# V2.net
KiCad netlist of a schematic drawn in EAGLE
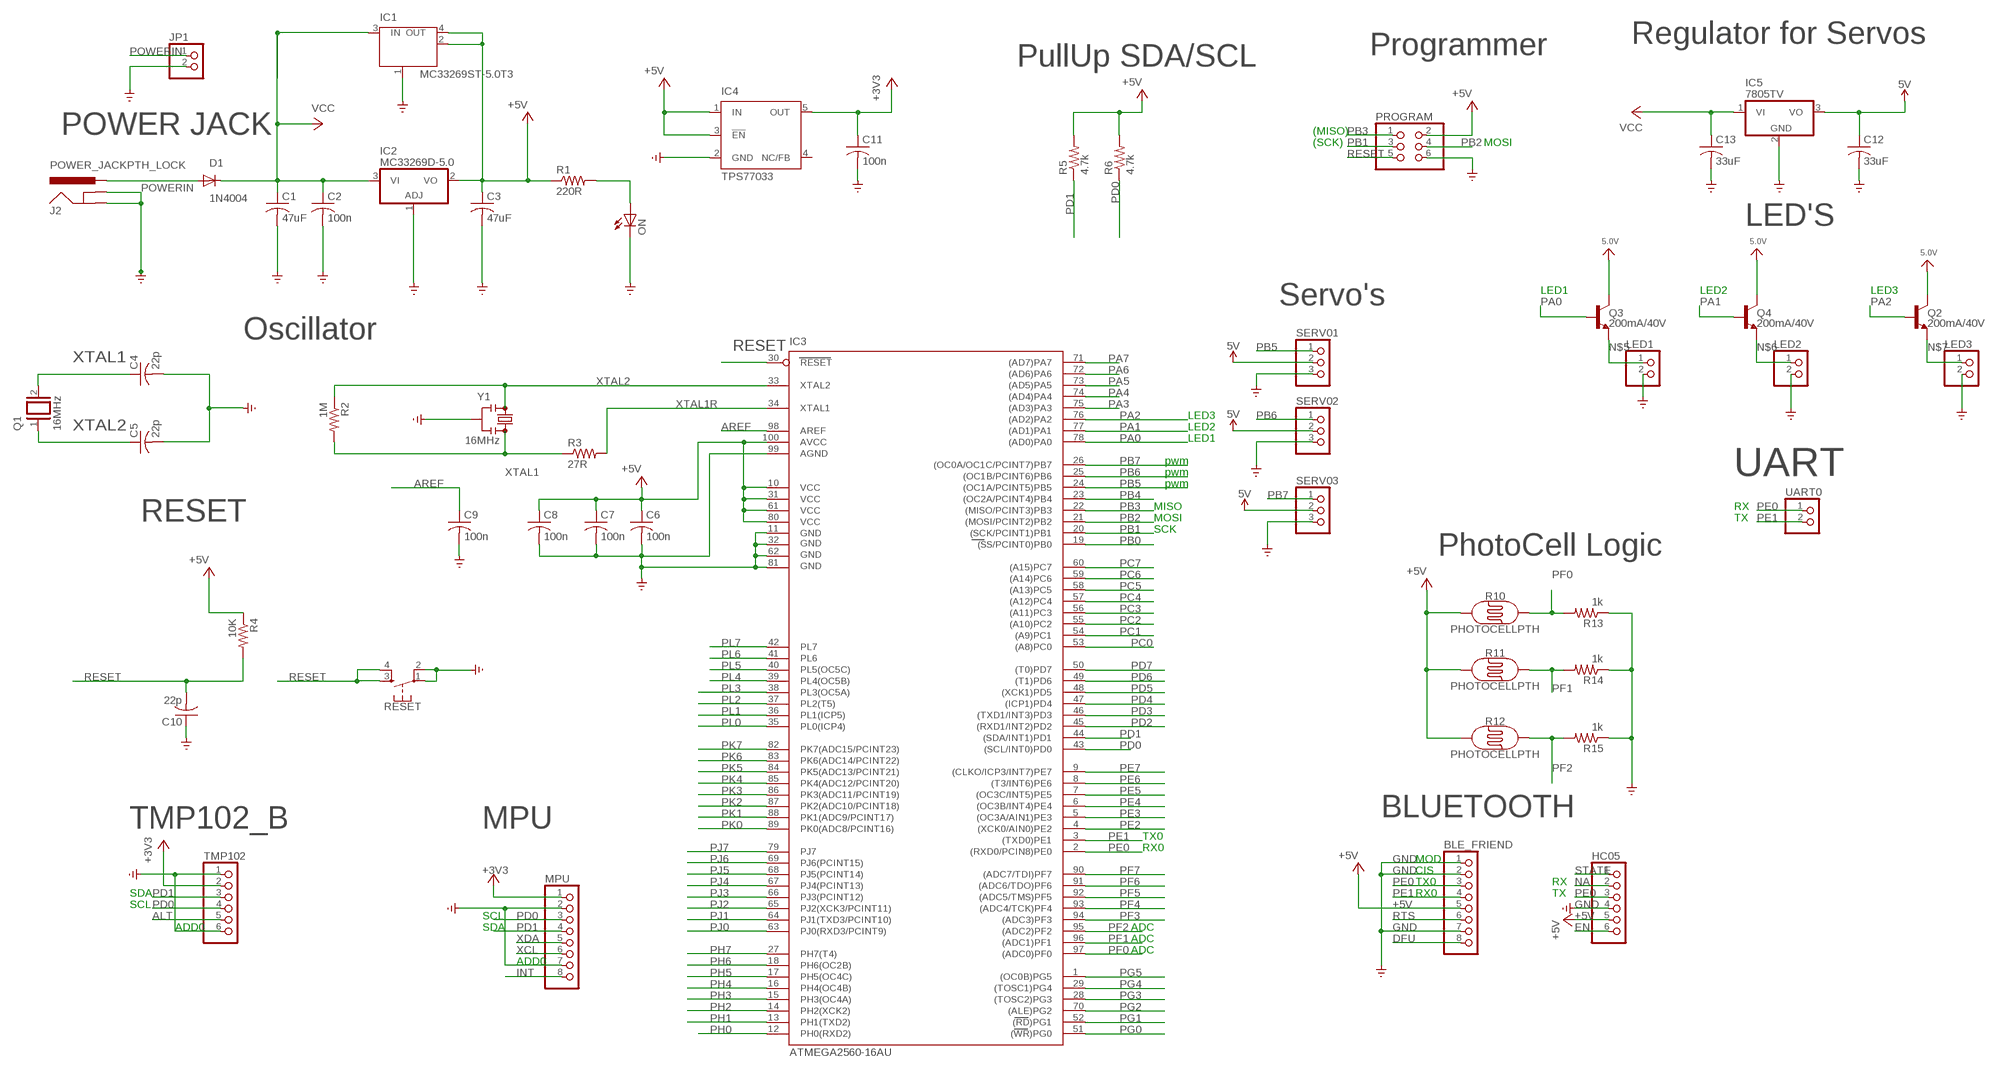
[diagram p0: schematic, sheet 1, part 1 of 2]
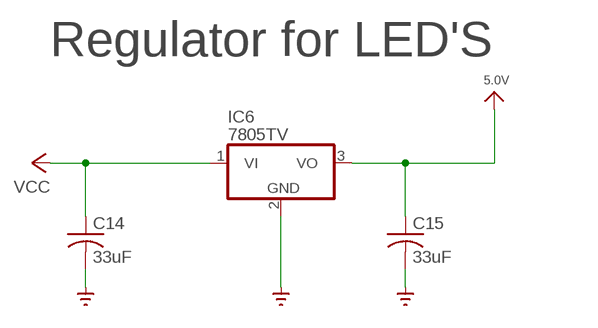
[diagram p1: schematic, sheet 1, part 2 of 2]

(export (version "E")
  (design (tool "Eeschema 10.0.6"))
  (components
    (comp (ref "BLE_FRIEND")
      (value "PINHD-1X8")
      (footprint "eagle-import:1X08")
      (libsource (lib "eagle-import") (part "PINHD-1X8"))
    )
    (comp (ref "C1")
      (value "47uF")
      (footprint "eagle-import:C025-024X044")
      (libsource (lib "eagle-import") (part "C-US025-024X044"))
    )
    (comp (ref "C2")
      (value "100n")
      (footprint "eagle-import:C025-024X044")
      (libsource (lib "eagle-import") (part "C-US025-024X044"))
    )
    (comp (ref "C3")
      (value "47uF")
      (footprint "eagle-import:C025-024X044")
      (libsource (lib "eagle-import") (part "C-US025-024X044"))
    )
    (comp (ref "C4")
      (value "22p")
      (footprint "eagle-import:C025-024X044")
      (libsource (lib "eagle-import") (part "C-US025-024X044"))
    )
    (comp (ref "C5")
      (value "22p")
      (footprint "eagle-import:C025-024X044")
      (libsource (lib "eagle-import") (part "C-US025-024X044"))
    )
    (comp (ref "C6")
      (value "100n")
      (footprint "eagle-import:C025-024X044")
      (libsource (lib "eagle-import") (part "C-US025-024X044"))
    )
    (comp (ref "C7")
      (value "100n")
      (footprint "eagle-import:C025-024X044")
      (libsource (lib "eagle-import") (part "C-US025-024X044"))
    )
    (comp (ref "C8")
      (value "100n")
      (footprint "eagle-import:C025-024X044")
      (libsource (lib "eagle-import") (part "C-US025-024X044"))
    )
    (comp (ref "C9")
      (value "100n")
      (footprint "eagle-import:C025-024X044")
      (libsource (lib "eagle-import") (part "C-US025-024X044"))
    )
    (comp (ref "C10")
      (value "22p")
      (footprint "eagle-import:C025-024X044")
      (libsource (lib "eagle-import") (part "C-US025-024X044"))
    )
    (comp (ref "C11")
      (value "100n")
      (footprint "eagle-import:C025-024X044")
      (libsource (lib "eagle-import") (part "C-US025-024X044"))
    )
    (comp (ref "C12")
      (value "33uF")
      (footprint "eagle-import:C025-024X044")
      (libsource (lib "eagle-import") (part "C-US025-024X044"))
    )
    (comp (ref "C13")
      (value "33uF")
      (footprint "eagle-import:C025-024X044")
      (libsource (lib "eagle-import") (part "C-US025-024X044"))
    )
    (comp (ref "C14")
      (value "33uF")
      (footprint "eagle-import:C025-024X044")
      (libsource (lib "eagle-import") (part "C-US025-024X044"))
    )
    (comp (ref "C15")
      (value "33uF")
      (footprint "eagle-import:C025-024X044")
      (libsource (lib "eagle-import") (part "C-US025-024X044"))
    )
    (comp (ref "D1")
      (value "1N4004")
      (footprint "eagle-import:DO41-10")
      (libsource (lib "eagle-import") (part "1N4004"))
    )
    (comp (ref "HC05")
      (value "PINHD-1X6")
      (footprint "eagle-import:1X06")
      (libsource (lib "eagle-import") (part "pinhead_325_PINHD-1X6"))
    )
    (comp (ref "IC1")
      (value "MC33269ST-5.0T3")
      (footprint "eagle-import:SOT223")
      (libsource (lib "eagle-import") (part "MC33269ST-3.3T3"))
    )
    (comp (ref "IC2")
      (value "MC33269D-5.0")
      (footprint "eagle-import:DPACK")
      (libsource (lib "eagle-import") (part "MC33269?D-5.0"))
    )
    (comp (ref "IC3")
      (value "ATMEGA2560-16AU")
      (footprint "eagle-import:TQFP100")
      (libsource (lib "eagle-import") (part "ATMEGAAU2560-16"))
    )
    (comp (ref "IC4")
      (value "TPS77033")
      (footprint "eagle-import:SOT23-DBV")
      (fields (field (name "MF") "TEXAS INSTRUMENTS") (field (name "MPN") "TPS77033DBVT"))
      (libsource (lib "eagle-import") (part "TPS77033"))
    )
    (comp (ref "IC5")
      (value "7805TV")
      (footprint "eagle-import:TO220V")
      (libsource (lib "eagle-import") (part "78TV05"))
    )
    (comp (ref "IC6")
      (value "7805TV")
      (footprint "eagle-import:TO220V")
      (libsource (lib "eagle-import") (part "78TV05"))
    )
    (comp (ref "J2")
      (value "POWER_JACKPTH_LOCK")
      (footprint "eagle-import:POWER_JACK_PTH_LOCK")
      (libsource (lib "eagle-import") (part "POWER_JACKPTH_LOCK"))
    )
    (comp (ref "JP1")
      (value "PINHD-1X2")
      (footprint "eagle-import:1X02")
      (libsource (lib "eagle-import") (part "pinhead_325_PINHD-1X2"))
    )
    (comp (ref "LED1")
      (value "PINHD-1X2")
      (footprint "eagle-import:1X02")
      (libsource (lib "eagle-import") (part "PINHD-1X2"))
    )
    (comp (ref "LED2")
      (value "PINHD-1X2")
      (footprint "eagle-import:1X02")
      (libsource (lib "eagle-import") (part "PINHD-1X2"))
    )
    (comp (ref "LED3")
      (value "PINHD-1X2")
      (footprint "eagle-import:1X02")
      (libsource (lib "eagle-import") (part "PINHD-1X2"))
    )
    (comp (ref "MPU")
      (value "PINHD-1X8")
      (footprint "eagle-import:1X08")
      (libsource (lib "eagle-import") (part "PINHD-1X8"))
    )
    (comp (ref "ON")
      (value "LED3MM")
      (footprint "eagle-import:LED3MM")
      (libsource (lib "eagle-import") (part "LED3MM"))
    )
    (comp (ref "PROGRAM")
      (value "PINHD-2X3")
      (footprint "eagle-import:2X03")
      (libsource (lib "eagle-import") (part "PINHD-2X3"))
    )
    (comp (ref "Q1")
      (value "16MHz")
      (footprint "eagle-import:QS")
      (libsource (lib "eagle-import") (part "XTAL/S"))
    )
    (comp (ref "Q2")
      (value "200mA/40V")
      (footprint "eagle-import:TO-92")
      (libsource (lib "eagle-import") (part "TRANS_NPN-2N3904"))
    )
    (comp (ref "Q3")
      (value "200mA/40V")
      (footprint "eagle-import:TO-92")
      (libsource (lib "eagle-import") (part "TRANS_NPN-2N3904"))
    )
    (comp (ref "Q4")
      (value "200mA/40V")
      (footprint "eagle-import:TO-92")
      (libsource (lib "eagle-import") (part "TRANS_NPN-2N3904"))
    )
    (comp (ref "R1")
      (value "220R")
      (footprint "eagle-import:0204V")
      (libsource (lib "eagle-import") (part "R-US_0204/2V"))
    )
    (comp (ref "R2")
      (value "1M")
      (footprint "eagle-import:0204V")
      (libsource (lib "eagle-import") (part "R-US_0204/2V"))
    )
    (comp (ref "R3")
      (value "27R")
      (footprint "eagle-import:0204V")
      (libsource (lib "eagle-import") (part "R-US_0204/2V"))
    )
    (comp (ref "R4")
      (value "10K")
      (footprint "eagle-import:0204V")
      (libsource (lib "eagle-import") (part "R-US_0204/2V"))
    )
    (comp (ref "R5")
      (value "4.7k")
      (footprint "eagle-import:0204V")
      (libsource (lib "eagle-import") (part "R-US_0204/2V"))
    )
    (comp (ref "R6")
      (value "4.7k")
      (footprint "eagle-import:0204V")
      (libsource (lib "eagle-import") (part "R-US_0204/2V"))
    )
    (comp (ref "R10")
      (value "PHOTOCELLPTH")
      (footprint "eagle-import:PHOTOCELL")
      (libsource (lib "eagle-import") (part "PHOTOCELLPTH"))
    )
    (comp (ref "R11")
      (value "PHOTOCELLPTH")
      (footprint "eagle-import:PHOTOCELL")
      (libsource (lib "eagle-import") (part "PHOTOCELLPTH"))
    )
    (comp (ref "R12")
      (value "PHOTOCELLPTH")
      (footprint "eagle-import:PHOTOCELL")
      (libsource (lib "eagle-import") (part "PHOTOCELLPTH"))
    )
    (comp (ref "R13")
      (value "1k")
      (footprint "eagle-import:0204V")
      (libsource (lib "eagle-import") (part "R-US_0204/2V"))
    )
    (comp (ref "R14")
      (value "1k")
      (footprint "eagle-import:0204V")
      (libsource (lib "eagle-import") (part "R-US_0204/2V"))
    )
    (comp (ref "R15")
      (value "1k")
      (footprint "eagle-import:0204V")
      (libsource (lib "eagle-import") (part "R-US_0204/2V"))
    )
    (comp (ref "RESET")
      (value "MOMENTARY-SWITCH-SPST-2-SMD-5.2MM")
      (footprint "eagle-import:TACTILE_SWITCH_SMD_5.2MM")
      (libsource (lib "eagle-import") (part "MOMENTARY-SWITCH-SPST-2-SMD-5.2MM"))
    )
    (comp (ref "SERV01")
      (value "PINHD-1X3")
      (footprint "eagle-import:1X03")
      (libsource (lib "eagle-import") (part "PINHD-1X3"))
    )
    (comp (ref "SERV02")
      (value "PINHD-1X3")
      (footprint "eagle-import:1X03")
      (libsource (lib "eagle-import") (part "PINHD-1X3"))
    )
    (comp (ref "SERV03")
      (value "PINHD-1X3")
      (footprint "eagle-import:1X03")
      (libsource (lib "eagle-import") (part "PINHD-1X3"))
    )
    (comp (ref "TMP102")
      (value "PINHD-1X6")
      (footprint "eagle-import:1X06")
      (libsource (lib "eagle-import") (part "PINHD-1X6"))
    )
    (comp (ref "UART0")
      (value "PINHD-1X2")
      (footprint "eagle-import:1X02")
      (libsource (lib "eagle-import") (part "PINHD-1X2"))
    )
    (comp (ref "Y1")
      (value "16MHz")
      (footprint "eagle-import:RESONATOR-SMD-3.2X1.3")
      (libsource (lib "eagle-import") (part "RESONATORSMD-3.2X1.3"))
    )
  )
  (nets
    (net (code "1") (name "+3V3") (class "Default")
      (node (ref "C11") (pin "1") (pinfunction "1_1") (pintype "passive"))
      (node (ref "IC4") (pin "5") (pinfunction "OUT_5") (pintype "passive"))
      (node (ref "MPU") (pin "1") (pinfunction "1_1") (pintype "passive"))
      (node (ref "TMP102") (pin "2") (pinfunction "2_2") (pintype "passive"))
    )
    (net (code "2") (name "+5V") (class "Default")
      (node (ref "BLE_FRIEND") (pin "5") (pinfunction "5_5") (pintype "passive"))
      (node (ref "C3") (pin "1") (pinfunction "1_1") (pintype "passive"))
      (node (ref "C6") (pin "1") (pinfunction "1_1") (pintype "passive"))
      (node (ref "C7") (pin "1") (pinfunction "1_1") (pintype "passive"))
      (node (ref "C8") (pin "1") (pinfunction "1_1") (pintype "passive"))
      (node (ref "HC05") (pin "5") (pinfunction "5_5") (pintype "passive"))
      (node (ref "IC1") (pin "2") (pinfunction "OUT_2") (pintype "passive"))
      (node (ref "IC1") (pin "4") (pinfunction "OUT_4") (pintype "passive"))
      (node (ref "IC2") (pin "2") (pinfunction "VO_2") (pintype "passive"))
      (node (ref "IC3") (pin "10") (pinfunction "VCC_10") (pintype "power_in"))
      (node (ref "IC3") (pin "100") (pinfunction "AVCC_100") (pintype "power_in"))
      (node (ref "IC3") (pin "31") (pinfunction "VCC1_31") (pintype "power_in"))
      (node (ref "IC3") (pin "61") (pinfunction "VCC2_61") (pintype "power_in"))
      (node (ref "IC3") (pin "80") (pinfunction "VCC3_80") (pintype "power_in"))
      (node (ref "IC4") (pin "1") (pinfunction "IN_1") (pintype "input"))
      (node (ref "IC4") (pin "3") (pinfunction "~{EN}_3") (pintype "input"))
      (node (ref "PROGRAM") (pin "2") (pinfunction "2_2") (pintype "passive"))
      (node (ref "R1") (pin "1") (pinfunction "1_1") (pintype "passive"))
      (node (ref "R10") (pin "1") (pinfunction "P$1_1") (pintype "bidirectional"))
      (node (ref "R11") (pin "1") (pinfunction "P$1_1") (pintype "bidirectional"))
      (node (ref "R12") (pin "1") (pinfunction "P$1_1") (pintype "bidirectional"))
      (node (ref "R4") (pin "1") (pinfunction "1_1") (pintype "passive"))
      (node (ref "R5") (pin "2") (pinfunction "2_2") (pintype "passive"))
      (node (ref "R6") (pin "2") (pinfunction "2_2") (pintype "passive"))
    )
    (net (code "3") (name "/ALT") (class "Default")
      (node (ref "TMP102") (pin "5") (pinfunction "5_5") (pintype "passive"))
    )
    (net (code "4") (name "/AREF") (class "Default")
      (node (ref "C9") (pin "1") (pinfunction "1_1") (pintype "passive"))
      (node (ref "IC3") (pin "98") (pinfunction "AREF_98") (pintype "bidirectional"))
    )
    (net (code "5") (name "/DFU") (class "Default")
      (node (ref "BLE_FRIEND") (pin "8") (pinfunction "8_8") (pintype "passive"))
    )
    (net (code "6") (name "/EN") (class "Default")
      (node (ref "HC05") (pin "6") (pinfunction "6_6") (pintype "passive"))
    )
    (net (code "7") (name "/INT") (class "Default")
      (node (ref "MPU") (pin "8") (pinfunction "8_8") (pintype "passive"))
    )
    (net (code "8") (name "/N$5") (class "Default")
      (node (ref "LED1") (pin "1") (pinfunction "1_1") (pintype "passive"))
      (node (ref "Q3") (pin "1") (pinfunction "E_1") (pintype "passive"))
    )
    (net (code "9") (name "/N$6") (class "Default")
      (node (ref "LED2") (pin "1") (pinfunction "1_1") (pintype "passive"))
      (node (ref "Q4") (pin "1") (pinfunction "E_1") (pintype "passive"))
    )
    (net (code "10") (name "/N$7") (class "Default")
      (node (ref "LED3") (pin "1") (pinfunction "1_1") (pintype "passive"))
      (node (ref "Q2") (pin "1") (pinfunction "E_1") (pintype "passive"))
    )
    (net (code "11") (name "/NA") (class "Default")
      (node (ref "HC05") (pin "2") (pinfunction "2_2") (pintype "passive"))
    )
    (net (code "12") (name "/PA0") (class "Default")
      (node (ref "IC3") (pin "78") (pinfunction "(AD0)PA0_78") (pintype "bidirectional"))
      (node (ref "Q3") (pin "2") (pinfunction "B_2") (pintype "passive"))
    )
    (net (code "13") (name "/PA1") (class "Default")
      (node (ref "IC3") (pin "77") (pinfunction "(AD1)PA1_77") (pintype "bidirectional"))
      (node (ref "Q4") (pin "2") (pinfunction "B_2") (pintype "passive"))
    )
    (net (code "14") (name "/PA2") (class "Default")
      (node (ref "IC3") (pin "76") (pinfunction "(AD2)PA2_76") (pintype "bidirectional"))
      (node (ref "Q2") (pin "2") (pinfunction "B_2") (pintype "passive"))
    )
    (net (code "15") (name "/PA3") (class "Default")
      (node (ref "IC3") (pin "75") (pinfunction "(AD3)PA3_75") (pintype "bidirectional"))
    )
    (net (code "16") (name "/PA4") (class "Default")
      (node (ref "IC3") (pin "74") (pinfunction "(AD4)PA4_74") (pintype "bidirectional"))
    )
    (net (code "17") (name "/PA5") (class "Default")
      (node (ref "IC3") (pin "73") (pinfunction "(AD5)PA5_73") (pintype "bidirectional"))
    )
    (net (code "18") (name "/PA6") (class "Default")
      (node (ref "IC3") (pin "72") (pinfunction "(AD6)PA6_72") (pintype "bidirectional"))
    )
    (net (code "19") (name "/PA7") (class "Default")
      (node (ref "IC3") (pin "71") (pinfunction "(AD7)PA7_71") (pintype "bidirectional"))
    )
    (net (code "20") (name "/PB0") (class "Default")
      (node (ref "IC3") (pin "19") (pinfunction "(SS/PCINT0)PB0_19") (pintype "bidirectional"))
    )
    (net (code "21") (name "/PB1") (class "Default")
      (node (ref "IC3") (pin "20") (pinfunction "(SCK/PCINT1)PB1_20") (pintype "bidirectional"))
      (node (ref "PROGRAM") (pin "3") (pinfunction "3_3") (pintype "passive"))
    )
    (net (code "22") (name "/PB2") (class "Default")
      (node (ref "IC3") (pin "21") (pinfunction "(MOSI/PCINT2)PB2_21") (pintype "bidirectional"))
      (node (ref "PROGRAM") (pin "4") (pinfunction "4_4") (pintype "passive"))
    )
    (net (code "23") (name "/PB3") (class "Default")
      (node (ref "IC3") (pin "22") (pinfunction "(MISO/PCINT3)PB3_22") (pintype "bidirectional"))
      (node (ref "PROGRAM") (pin "1") (pinfunction "1_1") (pintype "passive"))
    )
    (net (code "24") (name "/PB4") (class "Default")
      (node (ref "IC3") (pin "23") (pinfunction "(OC2A/PCINT4)PB4_23") (pintype "bidirectional"))
    )
    (net (code "25") (name "/PB5") (class "Default")
      (node (ref "IC3") (pin "24") (pinfunction "(OC1A/PCINT5)PB5_24") (pintype "bidirectional"))
      (node (ref "SERV01") (pin "1") (pinfunction "1_1") (pintype "passive"))
    )
    (net (code "26") (name "/PB6") (class "Default")
      (node (ref "IC3") (pin "25") (pinfunction "(OC1B/PCINT6)PB6_25") (pintype "bidirectional"))
      (node (ref "SERV02") (pin "1") (pinfunction "1_1") (pintype "passive"))
    )
    (net (code "27") (name "/PB7") (class "Default")
      (node (ref "IC3") (pin "26") (pinfunction "(OC0A/OC1C/PCINT7)PB7_26") (pintype "bidirectional"))
      (node (ref "SERV03") (pin "1") (pinfunction "1_1") (pintype "passive"))
    )
    (net (code "28") (name "/PC0") (class "Default")
      (node (ref "IC3") (pin "53") (pinfunction "(A8)PC0_53") (pintype "bidirectional"))
    )
    (net (code "29") (name "/PC1") (class "Default")
      (node (ref "IC3") (pin "54") (pinfunction "(A9)PC1_54") (pintype "bidirectional"))
    )
    (net (code "30") (name "/PC2") (class "Default")
      (node (ref "IC3") (pin "55") (pinfunction "(A10)PC2_55") (pintype "bidirectional"))
    )
    (net (code "31") (name "/PC3") (class "Default")
      (node (ref "IC3") (pin "56") (pinfunction "(A11)PC3_56") (pintype "bidirectional"))
    )
    (net (code "32") (name "/PC4") (class "Default")
      (node (ref "IC3") (pin "57") (pinfunction "(A12)PC4_57") (pintype "bidirectional"))
    )
    (net (code "33") (name "/PC5") (class "Default")
      (node (ref "IC3") (pin "58") (pinfunction "(A13)PC5_58") (pintype "bidirectional"))
    )
    (net (code "34") (name "/PC6") (class "Default")
      (node (ref "IC3") (pin "59") (pinfunction "(A14)PC6_59") (pintype "bidirectional"))
    )
    (net (code "35") (name "/PC7") (class "Default")
      (node (ref "IC3") (pin "60") (pinfunction "(A15)PC7_60") (pintype "bidirectional"))
    )
    (net (code "36") (name "/PD0") (class "Default")
      (node (ref "IC3") (pin "43") (pinfunction "(SCL/INT0)PD0_43") (pintype "bidirectional"))
      (node (ref "MPU") (pin "3") (pinfunction "3_3") (pintype "passive"))
      (node (ref "R6") (pin "1") (pinfunction "1_1") (pintype "passive"))
      (node (ref "TMP102") (pin "4") (pinfunction "4_4") (pintype "passive"))
    )
    (net (code "37") (name "/PD1") (class "Default")
      (node (ref "IC3") (pin "44") (pinfunction "(SDA/INT1)PD1_44") (pintype "bidirectional"))
      (node (ref "MPU") (pin "4") (pinfunction "4_4") (pintype "passive"))
      (node (ref "R5") (pin "1") (pinfunction "1_1") (pintype "passive"))
      (node (ref "TMP102") (pin "3") (pinfunction "3_3") (pintype "passive"))
    )
    (net (code "38") (name "/PD2") (class "Default")
      (node (ref "IC3") (pin "45") (pinfunction "(RXD1/INT2)PD2_45") (pintype "bidirectional"))
    )
    (net (code "39") (name "/PD3") (class "Default")
      (node (ref "IC3") (pin "46") (pinfunction "(TXD1/INT3)PD3_46") (pintype "bidirectional"))
    )
    (net (code "40") (name "/PD4") (class "Default")
      (node (ref "IC3") (pin "47") (pinfunction "(ICP1)PD4_47") (pintype "bidirectional"))
    )
    (net (code "41") (name "/PD5") (class "Default")
      (node (ref "IC3") (pin "48") (pinfunction "(XCK1)PD5_48") (pintype "bidirectional"))
    )
    (net (code "42") (name "/PD6") (class "Default")
      (node (ref "IC3") (pin "49") (pinfunction "(T1)PD6_49") (pintype "bidirectional"))
    )
    (net (code "43") (name "/PD7") (class "Default")
      (node (ref "IC3") (pin "50") (pinfunction "(T0)PD7_50") (pintype "bidirectional"))
    )
    (net (code "44") (name "/PE0") (class "Default")
      (node (ref "BLE_FRIEND") (pin "3") (pinfunction "3_3") (pintype "passive"))
      (node (ref "HC05") (pin "3") (pinfunction "3_3") (pintype "passive"))
      (node (ref "IC3") (pin "2") (pinfunction "(RXD0/PCIN8)PE0_2") (pintype "bidirectional"))
      (node (ref "UART0") (pin "1") (pinfunction "1_1") (pintype "passive"))
    )
    (net (code "45") (name "/PE1") (class "Default")
      (node (ref "BLE_FRIEND") (pin "4") (pinfunction "4_4") (pintype "passive"))
      (node (ref "IC3") (pin "3") (pinfunction "(TXD0)PE1_3") (pintype "bidirectional"))
      (node (ref "UART0") (pin "2") (pinfunction "2_2") (pintype "passive"))
    )
    (net (code "46") (name "/PE2") (class "Default")
      (node (ref "IC3") (pin "4") (pinfunction "(XCK0/AIN0)PE2_4") (pintype "bidirectional"))
    )
    (net (code "47") (name "/PE3") (class "Default")
      (node (ref "IC3") (pin "5") (pinfunction "(OC3A/AIN1)PE3_5") (pintype "bidirectional"))
    )
    (net (code "48") (name "/PE4") (class "Default")
      (node (ref "IC3") (pin "6") (pinfunction "(OC3B/INT4)PE4_6") (pintype "bidirectional"))
    )
    (net (code "49") (name "/PE5") (class "Default")
      (node (ref "IC3") (pin "7") (pinfunction "(OC3C/INT5)PE5_7") (pintype "bidirectional"))
    )
    (net (code "50") (name "/PE6") (class "Default")
      (node (ref "IC3") (pin "8") (pinfunction "(T3/INT6)PE6_8") (pintype "bidirectional"))
    )
    (net (code "51") (name "/PE7") (class "Default")
      (node (ref "IC3") (pin "9") (pinfunction "(CLKO/ICP3/INT7)PE7_9") (pintype "bidirectional"))
    )
    (net (code "52") (name "/PF0") (class "Default")
      (node (ref "IC3") (pin "97") (pinfunction "(ADC0)PF0_97") (pintype "bidirectional"))
      (node (ref "R10") (pin "2") (pinfunction "P$2_2") (pintype "bidirectional"))
      (node (ref "R13") (pin "2") (pinfunction "2_2") (pintype "passive"))
    )
    (net (code "53") (name "/PF1") (class "Default")
      (node (ref "IC3") (pin "96") (pinfunction "(ADC1)PF1_96") (pintype "bidirectional"))
      (node (ref "R11") (pin "2") (pinfunction "P$2_2") (pintype "bidirectional"))
      (node (ref "R14") (pin "2") (pinfunction "2_2") (pintype "passive"))
    )
    (net (code "54") (name "/PF2") (class "Default")
      (node (ref "IC3") (pin "95") (pinfunction "(ADC2)PF2_95") (pintype "bidirectional"))
      (node (ref "R12") (pin "2") (pinfunction "P$2_2") (pintype "bidirectional"))
      (node (ref "R15") (pin "2") (pinfunction "2_2") (pintype "passive"))
    )
    (net (code "55") (name "/PF3") (class "Default")
      (node (ref "IC3") (pin "94") (pinfunction "(ADC3)PF3_94") (pintype "bidirectional"))
    )
    (net (code "56") (name "/PF4") (class "Default")
      (node (ref "IC3") (pin "93") (pinfunction "(ADC4/TCK)PF4_93") (pintype "bidirectional"))
    )
    (net (code "57") (name "/PF5") (class "Default")
      (node (ref "IC3") (pin "92") (pinfunction "(ADC5/TMS)PF5_92") (pintype "bidirectional"))
    )
    (net (code "58") (name "/PF6") (class "Default")
      (node (ref "IC3") (pin "91") (pinfunction "(ADC6/TDO)PF6_91") (pintype "bidirectional"))
    )
    (net (code "59") (name "/PF7") (class "Default")
      (node (ref "IC3") (pin "90") (pinfunction "(ADC7/TDI)PF7_90") (pintype "bidirectional"))
    )
    (net (code "60") (name "/PG0") (class "Default")
      (node (ref "IC3") (pin "51") (pinfunction "(WR)PG0_51") (pintype "bidirectional"))
    )
    (net (code "61") (name "/PG1") (class "Default")
      (node (ref "IC3") (pin "52") (pinfunction "(RD)PG1_52") (pintype "bidirectional"))
    )
    (net (code "62") (name "/PG2") (class "Default")
      (node (ref "IC3") (pin "70") (pinfunction "(ALE)PG2_70") (pintype "bidirectional"))
    )
    (net (code "63") (name "/PG3") (class "Default")
      (node (ref "IC3") (pin "28") (pinfunction "(TOSC2)PG3_28") (pintype "bidirectional"))
    )
    (net (code "64") (name "/PG4") (class "Default")
      (node (ref "IC3") (pin "29") (pinfunction "(TOSC1)PG4_29") (pintype "bidirectional"))
    )
    (net (code "65") (name "/PG5") (class "Default")
      (node (ref "IC3") (pin "1") (pinfunction "(OC0B)PG5_1") (pintype "bidirectional"))
    )
    (net (code "66") (name "/PH0") (class "Default")
      (node (ref "IC3") (pin "12") (pinfunction "PH0(RXD2)_12") (pintype "bidirectional"))
    )
    (net (code "67") (name "/PH1") (class "Default")
      (node (ref "IC3") (pin "13") (pinfunction "PH1(TXD2)_13") (pintype "bidirectional"))
    )
    (net (code "68") (name "/PH2") (class "Default")
      (node (ref "IC3") (pin "14") (pinfunction "PH2(XCK2)_14") (pintype "bidirectional"))
    )
    (net (code "69") (name "/PH3") (class "Default")
      (node (ref "IC3") (pin "15") (pinfunction "PH3(OC4A)_15") (pintype "bidirectional"))
    )
    (net (code "70") (name "/PH4") (class "Default")
      (node (ref "IC3") (pin "16") (pinfunction "PH4(OC4B)_16") (pintype "bidirectional"))
    )
    (net (code "71") (name "/PH5") (class "Default")
      (node (ref "IC3") (pin "17") (pinfunction "PH5(OC4C)_17") (pintype "bidirectional"))
    )
    (net (code "72") (name "/PH6") (class "Default")
      (node (ref "IC3") (pin "18") (pinfunction "PH6(OC2B)_18") (pintype "bidirectional"))
    )
    (net (code "73") (name "/PH7") (class "Default")
      (node (ref "IC3") (pin "27") (pinfunction "PH7(T4)_27") (pintype "bidirectional"))
    )
    (net (code "74") (name "/PJ0") (class "Default")
      (node (ref "IC3") (pin "63") (pinfunction "PJ0(RXD3/PCINT9)_63") (pintype "bidirectional"))
    )
    (net (code "75") (name "/PJ1") (class "Default")
      (node (ref "IC3") (pin "64") (pinfunction "PJ1(TXD3/PCINT10)_64") (pintype "bidirectional"))
    )
    (net (code "76") (name "/PJ2") (class "Default")
      (node (ref "IC3") (pin "65") (pinfunction "PJ2(XCK3/PCINT11)_65") (pintype "bidirectional"))
    )
    (net (code "77") (name "/PJ3") (class "Default")
      (node (ref "IC3") (pin "66") (pinfunction "PJ3(PCINT12)_66") (pintype "bidirectional"))
    )
    (net (code "78") (name "/PJ4") (class "Default")
      (node (ref "IC3") (pin "67") (pinfunction "PJ4(PCINT13)_67") (pintype "bidirectional"))
    )
    (net (code "79") (name "/PJ5") (class "Default")
      (node (ref "IC3") (pin "68") (pinfunction "PJ5(PCINT14)_68") (pintype "bidirectional"))
    )
    (net (code "80") (name "/PJ6") (class "Default")
      (node (ref "IC3") (pin "69") (pinfunction "PJ6(PCINT15)_69") (pintype "bidirectional"))
    )
    (net (code "81") (name "/PJ7") (class "Default")
      (node (ref "IC3") (pin "79") (pinfunction "PJ7_79") (pintype "bidirectional"))
    )
    (net (code "82") (name "/PK0") (class "Default")
      (node (ref "IC3") (pin "89") (pinfunction "PK0(ADC8/PCINT16)_89") (pintype "bidirectional"))
    )
    (net (code "83") (name "/PK1") (class "Default")
      (node (ref "IC3") (pin "88") (pinfunction "PK1(ADC9/PCINT17)_88") (pintype "bidirectional"))
    )
    (net (code "84") (name "/PK2") (class "Default")
      (node (ref "IC3") (pin "87") (pinfunction "PK2(ADC10/PCINT18)_87") (pintype "bidirectional"))
    )
    (net (code "85") (name "/PK3") (class "Default")
      (node (ref "IC3") (pin "86") (pinfunction "PK3(ADC11/PCINT19)_86") (pintype "bidirectional"))
    )
    (net (code "86") (name "/PK4") (class "Default")
      (node (ref "IC3") (pin "85") (pinfunction "PK4(ADC12/PCINT20)_85") (pintype "bidirectional"))
    )
    (net (code "87") (name "/PK5") (class "Default")
      (node (ref "IC3") (pin "84") (pinfunction "PK5(ADC13/PCINT21)_84") (pintype "bidirectional"))
    )
    (net (code "88") (name "/PK6") (class "Default")
      (node (ref "IC3") (pin "83") (pinfunction "PK6(ADC14/PCINT22)_83") (pintype "bidirectional"))
    )
    (net (code "89") (name "/PK7") (class "Default")
      (node (ref "IC3") (pin "82") (pinfunction "PK7(ADC15/PCINT23)_82") (pintype "bidirectional"))
    )
    (net (code "90") (name "/PL0") (class "Default")
      (node (ref "IC3") (pin "35") (pinfunction "PL0(ICP4)_35") (pintype "bidirectional"))
    )
    (net (code "91") (name "/PL1") (class "Default")
      (node (ref "IC3") (pin "36") (pinfunction "PL1(ICP5)_36") (pintype "bidirectional"))
    )
    (net (code "92") (name "/PL2") (class "Default")
      (node (ref "IC3") (pin "37") (pinfunction "PL2(T5)_37") (pintype "bidirectional"))
    )
    (net (code "93") (name "/PL3") (class "Default")
      (node (ref "IC3") (pin "38") (pinfunction "PL3(OC5A)_38") (pintype "bidirectional"))
    )
    (net (code "94") (name "/PL4") (class "Default")
      (node (ref "IC3") (pin "39") (pinfunction "PL4(OC5B)_39") (pintype "bidirectional"))
    )
    (net (code "95") (name "/PL5") (class "Default")
      (node (ref "IC3") (pin "40") (pinfunction "PL5(OC5C)_40") (pintype "bidirectional"))
    )
    (net (code "96") (name "/PL6") (class "Default")
      (node (ref "IC3") (pin "41") (pinfunction "PL6_41") (pintype "bidirectional"))
    )
    (net (code "97") (name "/PL7") (class "Default")
      (node (ref "IC3") (pin "42") (pinfunction "PL7_42") (pintype "bidirectional"))
    )
    (net (code "98") (name "/POWERIN") (class "Default")
      (node (ref "D1") (pin "A") (pinfunction "A_A") (pintype "passive"))
      (node (ref "J2") (pin "PWR") (pinfunction "PWR_PWR") (pintype "bidirectional"))
      (node (ref "JP1") (pin "1") (pinfunction "1_1") (pintype "passive"))
    )
    (net (code "99") (name "/RESET") (class "Default")
      (node (ref "C10") (pin "2") (pinfunction "2_2") (pintype "passive"))
      (node (ref "IC3") (pin "30") (pinfunction "RESET_30") (pintype "input"))
      (node (ref "PROGRAM") (pin "5") (pinfunction "5_5") (pintype "passive"))
      (node (ref "R4") (pin "2") (pinfunction "2_2") (pintype "passive"))
      (node (ref "RESET") (pin "3") (pinfunction "3_3") (pintype "passive"))
      (node (ref "RESET") (pin "4") (pinfunction "4_4") (pintype "passive"))
    )
    (net (code "100") (name "/RTS") (class "Default")
      (node (ref "BLE_FRIEND") (pin "6") (pinfunction "6_6") (pintype "passive"))
    )
    (net (code "101") (name "/STATE") (class "Default")
      (node (ref "HC05") (pin "1") (pinfunction "1_1") (pintype "passive"))
    )
    (net (code "102") (name "/XCL") (class "Default")
      (node (ref "MPU") (pin "6") (pinfunction "6_6") (pintype "passive"))
    )
    (net (code "103") (name "/XDA") (class "Default")
      (node (ref "MPU") (pin "5") (pinfunction "5_5") (pintype "passive"))
    )
    (net (code "104") (name "/XTAL1") (class "Default")
      (node (ref "C4") (pin "1") (pinfunction "1_1") (pintype "passive"))
      (node (ref "Q1") (pin "2") (pinfunction "2_2") (pintype "passive"))
      (node (ref "R2") (pin "2") (pinfunction "2_2") (pintype "passive"))
      (node (ref "R3") (pin "1") (pinfunction "1_1") (pintype "passive"))
      (node (ref "Y1") (pin "3") (pinfunction "3_3") (pintype "passive"))
    )
    (net (code "105") (name "/XTAL1R") (class "Default")
      (node (ref "IC3") (pin "34") (pinfunction "XTAL1_34") (pintype "input"))
      (node (ref "R3") (pin "2") (pinfunction "2_2") (pintype "passive"))
    )
    (net (code "106") (name "/XTAL2") (class "Default")
      (node (ref "C5") (pin "1") (pinfunction "1_1") (pintype "passive"))
      (node (ref "IC3") (pin "33") (pinfunction "XTAL2_33") (pintype "output"))
      (node (ref "Q1") (pin "1") (pinfunction "1_1") (pintype "passive"))
      (node (ref "R2") (pin "1") (pinfunction "1_1") (pintype "passive"))
      (node (ref "Y1") (pin "1") (pinfunction "1_1") (pintype "passive"))
    )
    (net (code "107") (name "5.0V") (class "Default")
      (node (ref "C15") (pin "1") (pinfunction "1_1") (pintype "passive"))
      (node (ref "IC6") (pin "3") (pinfunction "VO_3") (pintype "passive"))
      (node (ref "Q2") (pin "3") (pinfunction "C_3") (pintype "passive"))
      (node (ref "Q3") (pin "3") (pinfunction "C_3") (pintype "passive"))
      (node (ref "Q4") (pin "3") (pinfunction "C_3") (pintype "passive"))
    )
    (net (code "108") (name "5V") (class "Default")
      (node (ref "C12") (pin "1") (pinfunction "1_1") (pintype "passive"))
      (node (ref "IC5") (pin "3") (pinfunction "VO_3") (pintype "passive"))
      (node (ref "SERV01") (pin "2") (pinfunction "2_2") (pintype "passive"))
      (node (ref "SERV02") (pin "2") (pinfunction "2_2") (pintype "passive"))
      (node (ref "SERV03") (pin "2") (pinfunction "2_2") (pintype "passive"))
    )
    (net (code "109") (name "GND_") (class "Default")
      (node (ref "BLE_FRIEND") (pin "1") (pinfunction "1_1") (pintype "passive"))
      (node (ref "BLE_FRIEND") (pin "2") (pinfunction "2_2") (pintype "passive"))
      (node (ref "BLE_FRIEND") (pin "7") (pinfunction "7_7") (pintype "passive"))
      (node (ref "C1") (pin "2") (pinfunction "2_2") (pintype "passive"))
      (node (ref "C10") (pin "1") (pinfunction "1_1") (pintype "passive"))
      (node (ref "C11") (pin "2") (pinfunction "2_2") (pintype "passive"))
      (node (ref "C12") (pin "2") (pinfunction "2_2") (pintype "passive"))
      (node (ref "C13") (pin "2") (pinfunction "2_2") (pintype "passive"))
      (node (ref "C14") (pin "2") (pinfunction "2_2") (pintype "passive"))
      (node (ref "C15") (pin "2") (pinfunction "2_2") (pintype "passive"))
      (node (ref "C2") (pin "2") (pinfunction "2_2") (pintype "passive"))
      (node (ref "C3") (pin "2") (pinfunction "2_2") (pintype "passive"))
      (node (ref "C4") (pin "2") (pinfunction "2_2") (pintype "passive"))
      (node (ref "C5") (pin "2") (pinfunction "2_2") (pintype "passive"))
      (node (ref "C6") (pin "2") (pinfunction "2_2") (pintype "passive"))
      (node (ref "C7") (pin "2") (pinfunction "2_2") (pintype "passive"))
      (node (ref "C8") (pin "2") (pinfunction "2_2") (pintype "passive"))
      (node (ref "C9") (pin "2") (pinfunction "2_2") (pintype "passive"))
      (node (ref "HC05") (pin "4") (pinfunction "4_4") (pintype "passive"))
      (node (ref "IC1") (pin "1") (pinfunction "GND/ADJ_1") (pintype "input"))
      (node (ref "IC2") (pin "1") (pinfunction "ADJ_1") (pintype "input"))
      (node (ref "IC3") (pin "11") (pinfunction "GND_11") (pintype "power_in"))
      (node (ref "IC3") (pin "32") (pinfunction "GND1_32") (pintype "power_in"))
      (node (ref "IC3") (pin "62") (pinfunction "GND2_62") (pintype "power_in"))
      (node (ref "IC3") (pin "81") (pinfunction "GND3_81") (pintype "power_in"))
      (node (ref "IC3") (pin "99") (pinfunction "AGND_99") (pintype "power_in"))
      (node (ref "IC4") (pin "2") (pinfunction "GND_2") (pintype "power_in"))
      (node (ref "IC5") (pin "2") (pinfunction "GND_2") (pintype "passive"))
      (node (ref "IC6") (pin "2") (pinfunction "GND_2") (pintype "passive"))
      (node (ref "J2") (pin "GND") (pinfunction "GND_GND") (pintype "bidirectional"))
      (node (ref "J2") (pin "GNDBREAK") (pinfunction "GNDBREAK_GNDBREAK") (pintype "bidirectional"))
      (node (ref "JP1") (pin "2") (pinfunction "2_2") (pintype "passive"))
      (node (ref "LED1") (pin "2") (pinfunction "2_2") (pintype "passive"))
      (node (ref "LED2") (pin "2") (pinfunction "2_2") (pintype "passive"))
      (node (ref "LED3") (pin "2") (pinfunction "2_2") (pintype "passive"))
      (node (ref "MPU") (pin "2") (pinfunction "2_2") (pintype "passive"))
      (node (ref "MPU") (pin "7") (pinfunction "7_7") (pintype "passive"))
      (node (ref "ON") (pin "K") (pinfunction "C_K") (pintype "passive"))
      (node (ref "PROGRAM") (pin "6") (pinfunction "6_6") (pintype "passive"))
      (node (ref "R13") (pin "1") (pinfunction "1_1") (pintype "passive"))
      (node (ref "R14") (pin "1") (pinfunction "1_1") (pintype "passive"))
      (node (ref "R15") (pin "1") (pinfunction "1_1") (pintype "passive"))
      (node (ref "RESET") (pin "1") (pinfunction "1_1") (pintype "passive"))
      (node (ref "RESET") (pin "2") (pinfunction "2_2") (pintype "passive"))
      (node (ref "SERV01") (pin "3") (pinfunction "3_3") (pintype "passive"))
      (node (ref "SERV02") (pin "3") (pinfunction "3_3") (pintype "passive"))
      (node (ref "SERV03") (pin "3") (pinfunction "3_3") (pintype "passive"))
      (node (ref "TMP102") (pin "1") (pinfunction "1_1") (pintype "passive"))
      (node (ref "TMP102") (pin "6") (pinfunction "6_6") (pintype "passive"))
      (node (ref "Y1") (pin "2") (pinfunction "2_2") (pintype "passive"))
    )
    (net (code "110") (name "Net-(ON-PadA)") (class "Default")
      (node (ref "ON") (pin "A") (pinfunction "A_A") (pintype "passive"))
      (node (ref "R1") (pin "2") (pinfunction "2_2") (pintype "passive"))
    )
    (net (code "111") (name "VCC") (class "Default")
      (node (ref "C1") (pin "1") (pinfunction "1_1") (pintype "passive"))
      (node (ref "C13") (pin "1") (pinfunction "1_1") (pintype "passive"))
      (node (ref "C14") (pin "1") (pinfunction "1_1") (pintype "passive"))
      (node (ref "C2") (pin "1") (pinfunction "1_1") (pintype "passive"))
      (node (ref "D1") (pin "C") (pinfunction "C_C") (pintype "passive"))
      (node (ref "IC1") (pin "3") (pinfunction "IN_3") (pintype "input"))
      (node (ref "IC2") (pin "3") (pinfunction "VI_3") (pintype "input"))
      (node (ref "IC5") (pin "1") (pinfunction "VI_1") (pintype "input"))
      (node (ref "IC6") (pin "1") (pinfunction "VI_1") (pintype "input"))
    )
    (net (code "112") (name "unconnected-(IC4-NC{slash}FB-Pad4)") (class "Default")
      (node (ref "IC4") (pin "4") (pinfunction "NC/FB_4") (pintype "passive"))
    )
  )
)
